# Sheet1.net
KiCad netlist of a schematic drawn in Altium Designer
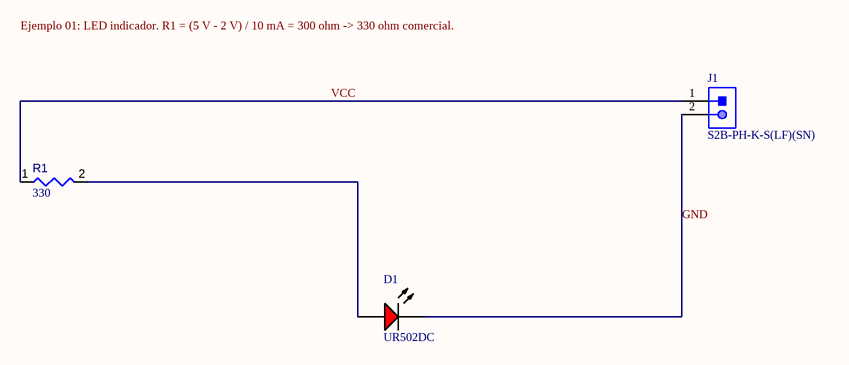
[diagram p0: Sheet1.SchDoc]

(export (version "E")
  (design (tool "Eeschema 10.0.6"))
  (components
    (comp (ref "D1")
      (value "UR502DC")
      (footprint "CGX-UR502DC")
      (description "Red LED, 80 mW, 30 mA, -25 to 85 degC, 2-Pin THD")
      (fields (field (name "POWER") "80mW") (field (name "MANUFACTURER") "Shenzhen CGX"))
      (libsource (lib "EFRAIN ALVARADO") (part "LED-RED-AK-2"))
    )
    (comp (ref "J1")
      (value "S2B-PH-K-S(LF)(SN)")
      (footprint "JST-S2B-PH-K-S_V")
      (fields (field (name "MANUFACTURER") "Japan Solderless Terminals"))
      (libsource (lib "EFRAIN ALVARADO") (part "CN-1P-M-R2"))
    )
    (comp (ref "R1")
      (value "330")
      (footprint "RESC0402(1005)_L")
      (description "Chip Resistor, 330 Ohms, +/-5 %, 63 mW, -55 to 155 degC, 0402")
      (fields (field (name "POWER") "63mW") (field (name "TOLERANCE") "5%"))
      (libsource (lib "EFRAIN ALVARADO") (part "RES-2"))
    )
  )
  (nets
    (net (code "1") (name "/GND") (class "Default")
      (node (ref "D1") (pin "2") (pinfunction "K_2") (pintype "passive"))
      (node (ref "J1") (pin "2") (pinfunction "2_2") (pintype "passive"))
    )
    (net (code "2") (name "/VCC") (class "Default")
      (node (ref "J1") (pin "1") (pinfunction "1_1") (pintype "passive"))
      (node (ref "R1") (pin "1") (pinfunction "1_1") (pintype "passive"))
    )
    (net (code "3") (name "Net-(D1-A)") (class "Default")
      (node (ref "D1") (pin "1") (pinfunction "A_1") (pintype "passive"))
      (node (ref "R1") (pin "2") (pinfunction "2_2") (pintype "passive"))
    )
  )
)
